# 4layer_test.net
KiCad netlist of a schematic drawn in EAGLE
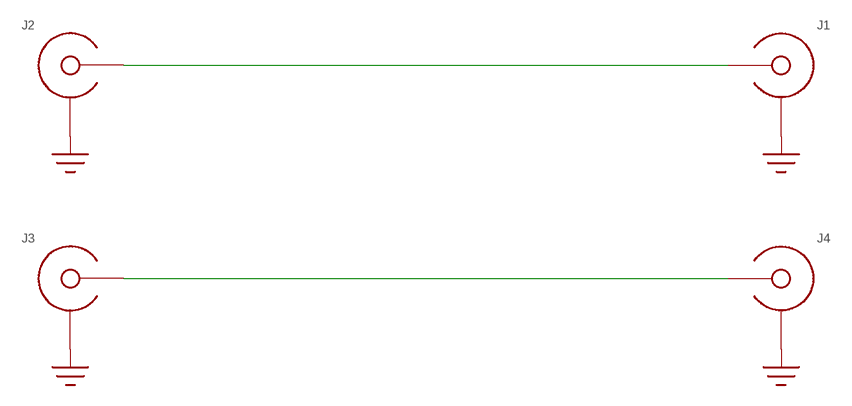
[diagram p0: schematic, sheet 1]

(export (version "E")
  (design (tool "Eeschema 10.0.6"))
  (components
    (comp (ref "J1")
      (value "SMA_END_LAUNCH4L")
      (footprint "eagle-import:SMA_EDGE_LAUNCH")
      (libsource (lib "eagle-import") (part "SMA_END_LAUNCH4L"))
    )
    (comp (ref "J2")
      (value "SMA_END_LAUNCH4L")
      (footprint "eagle-import:SMA_EDGE_LAUNCH")
      (libsource (lib "eagle-import") (part "SMA_END_LAUNCH4L"))
    )
    (comp (ref "J3")
      (value "SMA_END_LAUNCH4L")
      (footprint "eagle-import:SMA_EDGE_LAUNCH")
      (libsource (lib "eagle-import") (part "SMA_END_LAUNCH4L"))
    )
    (comp (ref "J4")
      (value "SMA_END_LAUNCH4L")
      (footprint "eagle-import:SMA_EDGE_LAUNCH")
      (libsource (lib "eagle-import") (part "SMA_END_LAUNCH4L"))
    )
  )
  (nets
    (net (code "1") (name "GND") (class "Default")
      (node (ref "J1") (pin "BOTTOM_PAD") (pinfunction "SHIELD_BOTTOM_PAD") (pintype "bidirectional"))
      (node (ref "J1") (pin "GND@1") (pinfunction "SHIELD_GND@1") (pintype "bidirectional"))
      (node (ref "J1") (pin "GND@14") (pinfunction "SHIELD_GND@14") (pintype "bidirectional"))
      (node (ref "J1") (pin "GND@15") (pinfunction "SHIELD_GND@15") (pintype "bidirectional"))
      (node (ref "J1") (pin "GND@16") (pinfunction "SHIELD_GND@16") (pintype "bidirectional"))
      (node (ref "J1") (pin "GND@17") (pinfunction "SHIELD_GND@17") (pintype "bidirectional"))
      (node (ref "J1") (pin "GND@2") (pinfunction "SHIELD_GND@2") (pintype "bidirectional"))
      (node (ref "J1") (pin "GND@3") (pinfunction "SHIELD_GND@3") (pintype "bidirectional"))
      (node (ref "J1") (pin "GND@4") (pinfunction "SHIELD_GND@4") (pintype "bidirectional"))
      (node (ref "J1") (pin "GND@5") (pinfunction "SHIELD_GND@5") (pintype "bidirectional"))
      (node (ref "J1") (pin "GND@6") (pinfunction "SHIELD_GND@6") (pintype "bidirectional"))
      (node (ref "J1") (pin "GND@7") (pinfunction "SHIELD_GND@7") (pintype "bidirectional"))
      (node (ref "J1") (pin "GND@8") (pinfunction "SHIELD_GND@8") (pintype "bidirectional"))
      (node (ref "J1") (pin "GND_PAD1") (pinfunction "SHIELD_GND_PAD1") (pintype "bidirectional"))
      (node (ref "J1") (pin "GND_PAD2") (pinfunction "SHIELD_GND_PAD2") (pintype "bidirectional"))
      (node (ref "J2") (pin "BOTTOM_PAD") (pinfunction "SHIELD_BOTTOM_PAD") (pintype "bidirectional"))
      (node (ref "J2") (pin "GND@1") (pinfunction "SHIELD_GND@1") (pintype "bidirectional"))
      (node (ref "J2") (pin "GND@14") (pinfunction "SHIELD_GND@14") (pintype "bidirectional"))
      (node (ref "J2") (pin "GND@15") (pinfunction "SHIELD_GND@15") (pintype "bidirectional"))
      (node (ref "J2") (pin "GND@16") (pinfunction "SHIELD_GND@16") (pintype "bidirectional"))
      (node (ref "J2") (pin "GND@17") (pinfunction "SHIELD_GND@17") (pintype "bidirectional"))
      (node (ref "J2") (pin "GND@2") (pinfunction "SHIELD_GND@2") (pintype "bidirectional"))
      (node (ref "J2") (pin "GND@3") (pinfunction "SHIELD_GND@3") (pintype "bidirectional"))
      (node (ref "J2") (pin "GND@4") (pinfunction "SHIELD_GND@4") (pintype "bidirectional"))
      (node (ref "J2") (pin "GND@5") (pinfunction "SHIELD_GND@5") (pintype "bidirectional"))
      (node (ref "J2") (pin "GND@6") (pinfunction "SHIELD_GND@6") (pintype "bidirectional"))
      (node (ref "J2") (pin "GND@7") (pinfunction "SHIELD_GND@7") (pintype "bidirectional"))
      (node (ref "J2") (pin "GND@8") (pinfunction "SHIELD_GND@8") (pintype "bidirectional"))
      (node (ref "J2") (pin "GND_PAD1") (pinfunction "SHIELD_GND_PAD1") (pintype "bidirectional"))
      (node (ref "J2") (pin "GND_PAD2") (pinfunction "SHIELD_GND_PAD2") (pintype "bidirectional"))
      (node (ref "J3") (pin "BOTTOM_PAD") (pinfunction "SHIELD_BOTTOM_PAD") (pintype "bidirectional"))
      (node (ref "J3") (pin "GND@1") (pinfunction "SHIELD_GND@1") (pintype "bidirectional"))
      (node (ref "J3") (pin "GND@14") (pinfunction "SHIELD_GND@14") (pintype "bidirectional"))
      (node (ref "J3") (pin "GND@15") (pinfunction "SHIELD_GND@15") (pintype "bidirectional"))
      (node (ref "J3") (pin "GND@16") (pinfunction "SHIELD_GND@16") (pintype "bidirectional"))
      (node (ref "J3") (pin "GND@17") (pinfunction "SHIELD_GND@17") (pintype "bidirectional"))
      (node (ref "J3") (pin "GND@2") (pinfunction "SHIELD_GND@2") (pintype "bidirectional"))
      (node (ref "J3") (pin "GND@3") (pinfunction "SHIELD_GND@3") (pintype "bidirectional"))
      (node (ref "J3") (pin "GND@4") (pinfunction "SHIELD_GND@4") (pintype "bidirectional"))
      (node (ref "J3") (pin "GND@5") (pinfunction "SHIELD_GND@5") (pintype "bidirectional"))
      (node (ref "J3") (pin "GND@6") (pinfunction "SHIELD_GND@6") (pintype "bidirectional"))
      (node (ref "J3") (pin "GND@7") (pinfunction "SHIELD_GND@7") (pintype "bidirectional"))
      (node (ref "J3") (pin "GND@8") (pinfunction "SHIELD_GND@8") (pintype "bidirectional"))
      (node (ref "J3") (pin "GND_PAD1") (pinfunction "SHIELD_GND_PAD1") (pintype "bidirectional"))
      (node (ref "J3") (pin "GND_PAD2") (pinfunction "SHIELD_GND_PAD2") (pintype "bidirectional"))
      (node (ref "J4") (pin "BOTTOM_PAD") (pinfunction "SHIELD_BOTTOM_PAD") (pintype "bidirectional"))
      (node (ref "J4") (pin "GND@1") (pinfunction "SHIELD_GND@1") (pintype "bidirectional"))
      (node (ref "J4") (pin "GND@14") (pinfunction "SHIELD_GND@14") (pintype "bidirectional"))
      (node (ref "J4") (pin "GND@15") (pinfunction "SHIELD_GND@15") (pintype "bidirectional"))
      (node (ref "J4") (pin "GND@16") (pinfunction "SHIELD_GND@16") (pintype "bidirectional"))
      (node (ref "J4") (pin "GND@17") (pinfunction "SHIELD_GND@17") (pintype "bidirectional"))
      (node (ref "J4") (pin "GND@2") (pinfunction "SHIELD_GND@2") (pintype "bidirectional"))
      (node (ref "J4") (pin "GND@3") (pinfunction "SHIELD_GND@3") (pintype "bidirectional"))
      (node (ref "J4") (pin "GND@4") (pinfunction "SHIELD_GND@4") (pintype "bidirectional"))
      (node (ref "J4") (pin "GND@5") (pinfunction "SHIELD_GND@5") (pintype "bidirectional"))
      (node (ref "J4") (pin "GND@6") (pinfunction "SHIELD_GND@6") (pintype "bidirectional"))
      (node (ref "J4") (pin "GND@7") (pinfunction "SHIELD_GND@7") (pintype "bidirectional"))
      (node (ref "J4") (pin "GND@8") (pinfunction "SHIELD_GND@8") (pintype "bidirectional"))
      (node (ref "J4") (pin "GND_PAD1") (pinfunction "SHIELD_GND_PAD1") (pintype "bidirectional"))
      (node (ref "J4") (pin "GND_PAD2") (pinfunction "SHIELD_GND_PAD2") (pintype "bidirectional"))
    )
    (net (code "2") (name "Net-(J1-CENTER-PadCENTER@1)") (class "Default")
      (node (ref "J1") (pin "CENTER@1") (pinfunction "CENTER_CENTER@1") (pintype "bidirectional"))
      (node (ref "J1") (pin "CENTER@2") (pinfunction "CENTER_CENTER@2") (pintype "bidirectional"))
      (node (ref "J2") (pin "CENTER@1") (pinfunction "CENTER_CENTER@1") (pintype "bidirectional"))
      (node (ref "J2") (pin "CENTER@2") (pinfunction "CENTER_CENTER@2") (pintype "bidirectional"))
    )
    (net (code "3") (name "Net-(J3-CENTER-PadCENTER@1)") (class "Default")
      (node (ref "J3") (pin "CENTER@1") (pinfunction "CENTER_CENTER@1") (pintype "bidirectional"))
      (node (ref "J3") (pin "CENTER@2") (pinfunction "CENTER_CENTER@2") (pintype "bidirectional"))
      (node (ref "J4") (pin "CENTER@1") (pinfunction "CENTER_CENTER@1") (pintype "bidirectional"))
      (node (ref "J4") (pin "CENTER@2") (pinfunction "CENTER_CENTER@2") (pintype "bidirectional"))
    )
  )
)
